# MultiWii_Board.net
KiCad netlist of a schematic drawn in EAGLE
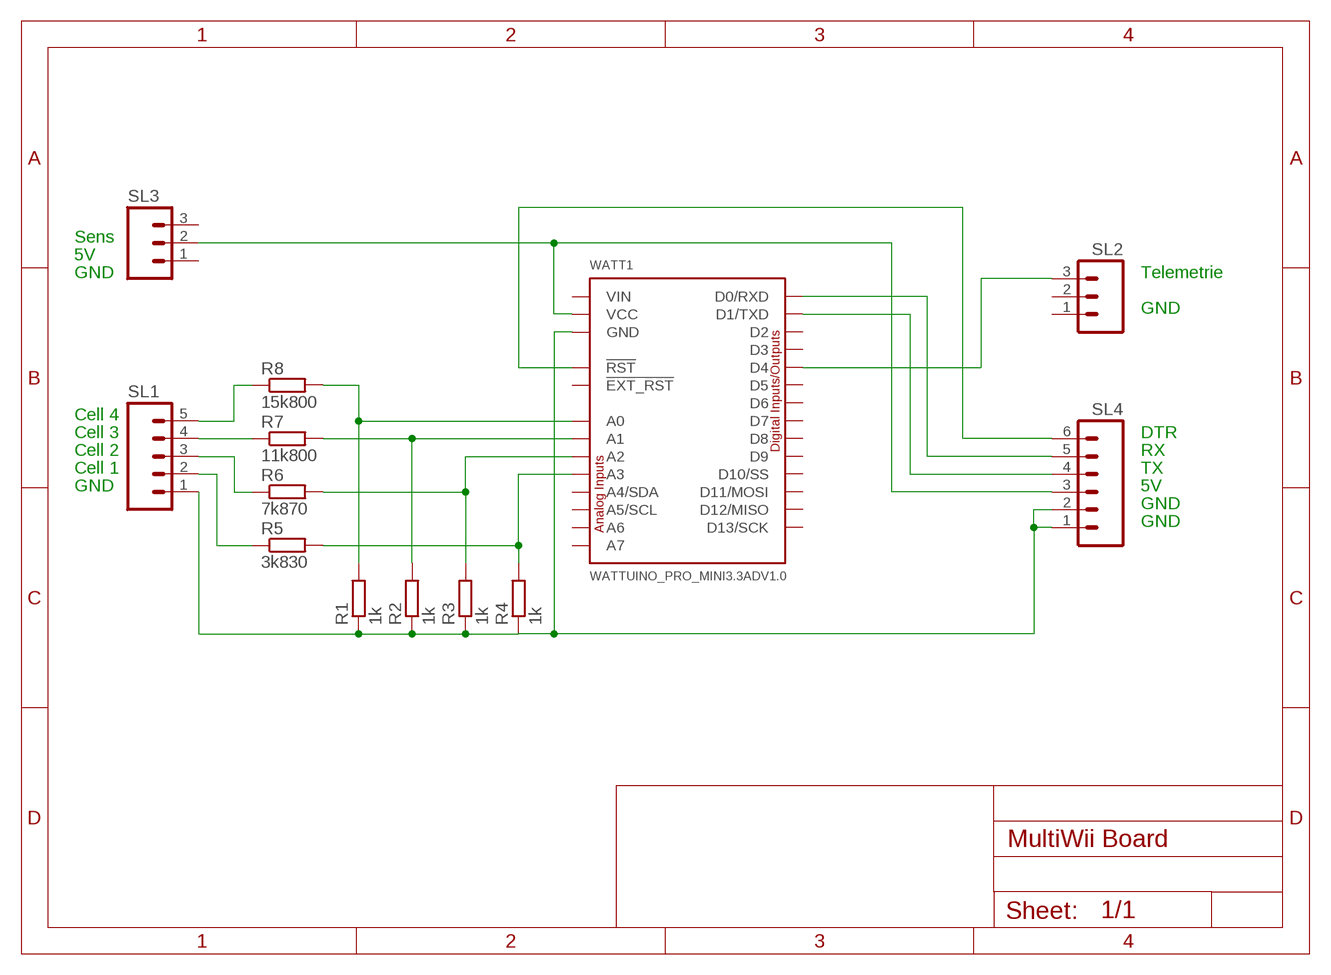
[diagram p0: schematic, sheet 1]

(export (version "E")
  (design (tool "Eeschema 10.0.6"))
  (components
    (comp (ref "R1")
      (value "1k")
      (footprint "eagle-import:0207_7")
      (libsource (lib "eagle-import") (part "R-EU_0207/7"))
    )
    (comp (ref "R2")
      (value "1k")
      (footprint "eagle-import:0207_7")
      (libsource (lib "eagle-import") (part "R-EU_0207/7"))
    )
    (comp (ref "R3")
      (value "1k")
      (footprint "eagle-import:0207_7")
      (libsource (lib "eagle-import") (part "R-EU_0207/7"))
    )
    (comp (ref "R4")
      (value "1k")
      (footprint "eagle-import:0207_7")
      (libsource (lib "eagle-import") (part "R-EU_0207/7"))
    )
    (comp (ref "R5")
      (value "3k830")
      (footprint "eagle-import:0207_7")
      (libsource (lib "eagle-import") (part "R-EU_0207/7"))
    )
    (comp (ref "R6")
      (value "7k870")
      (footprint "eagle-import:0207_7")
      (libsource (lib "eagle-import") (part "R-EU_0207/7"))
    )
    (comp (ref "R7")
      (value "11k800")
      (footprint "eagle-import:0207_7")
      (libsource (lib "eagle-import") (part "R-EU_0207/7"))
    )
    (comp (ref "R8")
      (value "15k800")
      (footprint "eagle-import:0207_7")
      (libsource (lib "eagle-import") (part "R-EU_0207/7"))
    )
    (comp (ref "SL1")
      (value "M05")
      (footprint "eagle-import:05P")
      (libsource (lib "eagle-import") (part "M05"))
    )
    (comp (ref "SL2")
      (value "M03")
      (footprint "eagle-import:03P")
      (libsource (lib "eagle-import") (part "M03"))
    )
    (comp (ref "SL3")
      (value "M03")
      (footprint "eagle-import:03P")
      (libsource (lib "eagle-import") (part "M03"))
    )
    (comp (ref "SL4")
      (value "M06")
      (footprint "eagle-import:06P")
      (libsource (lib "eagle-import") (part "M06"))
    )
    (comp (ref "WATT1")
      (value "WATTUINO_PRO_MINI3.3ADV1.0")
      (footprint "eagle-import:WATTUINO_PRO_MINI")
      (libsource (lib "eagle-import") (part "WATTUINO_PRO_MINIADV1.03.3"))
    )
  )
  (nets
    (net (code "1") (name "/VIN") (class "Default")
      (node (ref "WATT1") (pin "VIN") (pinfunction "VIN_VIN") (pintype "power_in"))
    )
    (net (code "2") (name "Net-(R1-Pad2)") (class "Default")
      (node (ref "R1") (pin "2") (pinfunction "2_2") (pintype "passive"))
      (node (ref "R8") (pin "2") (pinfunction "2_2") (pintype "passive"))
      (node (ref "WATT1") (pin "A0") (pinfunction "A0_A0") (pintype "input"))
    )
    (net (code "3") (name "Net-(R2-Pad2)") (class "Default")
      (node (ref "R2") (pin "2") (pinfunction "2_2") (pintype "passive"))
      (node (ref "R7") (pin "2") (pinfunction "2_2") (pintype "passive"))
      (node (ref "WATT1") (pin "A1") (pinfunction "A1_A1") (pintype "input"))
    )
    (net (code "4") (name "Net-(R3-Pad2)") (class "Default")
      (node (ref "R3") (pin "2") (pinfunction "2_2") (pintype "passive"))
      (node (ref "R6") (pin "2") (pinfunction "2_2") (pintype "passive"))
      (node (ref "WATT1") (pin "A2") (pinfunction "A2_A2") (pintype "input"))
    )
    (net (code "5") (name "Net-(R4-Pad2)") (class "Default")
      (node (ref "R4") (pin "2") (pinfunction "2_2") (pintype "passive"))
      (node (ref "R5") (pin "2") (pinfunction "2_2") (pintype "passive"))
      (node (ref "WATT1") (pin "A3") (pinfunction "A3_A3") (pintype "input"))
    )
    (net (code "6") (name "Net-(R5-Pad1)") (class "Default")
      (node (ref "R5") (pin "1") (pinfunction "1_1") (pintype "passive"))
      (node (ref "SL1") (pin "2") (pinfunction "2_2") (pintype "passive"))
    )
    (net (code "7") (name "Net-(R6-Pad1)") (class "Default")
      (node (ref "R6") (pin "1") (pinfunction "1_1") (pintype "passive"))
      (node (ref "SL1") (pin "3") (pinfunction "3_3") (pintype "passive"))
    )
    (net (code "8") (name "Net-(R7-Pad1)") (class "Default")
      (node (ref "R7") (pin "1") (pinfunction "1_1") (pintype "passive"))
      (node (ref "SL1") (pin "4") (pinfunction "4_4") (pintype "passive"))
    )
    (net (code "9") (name "Net-(R8-Pad1)") (class "Default")
      (node (ref "R8") (pin "1") (pinfunction "1_1") (pintype "passive"))
      (node (ref "SL1") (pin "5") (pinfunction "5_5") (pintype "passive"))
    )
    (net (code "10") (name "Net-(WATT1-D0{slash}RXD)") (class "Default")
      (node (ref "SL4") (pin "5") (pinfunction "5_5") (pintype "passive"))
      (node (ref "WATT1") (pin "RXD@1") (pinfunction "D0/RXD_RXD@1") (pintype "bidirectional"))
    )
    (net (code "11") (name "Net-(WATT1-D1{slash}TXD)") (class "Default")
      (node (ref "SL4") (pin "4") (pinfunction "4_4") (pintype "passive"))
      (node (ref "WATT1") (pin "TXD@1") (pinfunction "D1/TXD_TXD@1") (pintype "bidirectional"))
    )
    (net (code "12") (name "Net-(WATT1-D4)") (class "Default")
      (node (ref "SL2") (pin "3") (pinfunction "3_3") (pintype "passive"))
      (node (ref "WATT1") (pin "4") (pinfunction "D4_4") (pintype "bidirectional"))
    )
    (net (code "13") (name "Net-(WATT1-GND)") (class "Default")
      (node (ref "R1") (pin "1") (pinfunction "1_1") (pintype "passive"))
      (node (ref "R2") (pin "1") (pinfunction "1_1") (pintype "passive"))
      (node (ref "R3") (pin "1") (pinfunction "1_1") (pintype "passive"))
      (node (ref "R4") (pin "1") (pinfunction "1_1") (pintype "passive"))
      (node (ref "SL1") (pin "1") (pinfunction "1_1") (pintype "passive"))
      (node (ref "SL4") (pin "1") (pinfunction "1_1") (pintype "passive"))
      (node (ref "SL4") (pin "2") (pinfunction "2_2") (pintype "passive"))
      (node (ref "WATT1") (pin "GND@1") (pinfunction "GND_GND@1") (pintype "power_in"))
    )
    (net (code "14") (name "Net-(WATT1-VCC)") (class "Default")
      (node (ref "SL3") (pin "2") (pinfunction "2_2") (pintype "passive"))
      (node (ref "SL4") (pin "3") (pinfunction "3_3") (pintype "passive"))
      (node (ref "WATT1") (pin "VCC@1") (pinfunction "VCC_VCC@1") (pintype "power_in"))
    )
    (net (code "15") (name "Net-(WATT1-~{RST})") (class "Default")
      (node (ref "SL4") (pin "6") (pinfunction "6_6") (pintype "passive"))
      (node (ref "WATT1") (pin "RST@1") (pinfunction "~{RST}_RST@1") (pintype "input"))
    )
    (net (code "16") (name "unconnected-(SL2-Pad1)") (class "Default")
      (node (ref "SL2") (pin "1") (pinfunction "1_1") (pintype "passive"))
    )
    (net (code "17") (name "unconnected-(SL2-Pad2)") (class "Default")
      (node (ref "SL2") (pin "2") (pinfunction "2_2") (pintype "passive"))
    )
    (net (code "18") (name "unconnected-(SL3-Pad1)") (class "Default")
      (node (ref "SL3") (pin "1") (pinfunction "1_1") (pintype "passive"))
    )
    (net (code "19") (name "unconnected-(SL3-Pad3)") (class "Default")
      (node (ref "SL3") (pin "3") (pinfunction "3_3") (pintype "passive"))
    )
    (net (code "20") (name "unconnected-(WATT1-A4{slash}SDA-PadA4)") (class "Default")
      (node (ref "WATT1") (pin "A4") (pinfunction "A4/SDA_A4") (pintype "input"))
    )
    (net (code "21") (name "unconnected-(WATT1-A5{slash}SCL-PadA5)") (class "Default")
      (node (ref "WATT1") (pin "A5") (pinfunction "A5/SCL_A5") (pintype "input"))
    )
    (net (code "22") (name "unconnected-(WATT1-D2-Pad2)") (class "Default")
      (node (ref "WATT1") (pin "2") (pinfunction "D2_2") (pintype "bidirectional"))
    )
    (net (code "23") (name "unconnected-(WATT1-D3-Pad3)") (class "Default")
      (node (ref "WATT1") (pin "3") (pinfunction "D3_3") (pintype "bidirectional"))
    )
    (net (code "24") (name "unconnected-(WATT1-D5-Pad5)") (class "Default")
      (node (ref "WATT1") (pin "5") (pinfunction "D5_5") (pintype "bidirectional"))
    )
    (net (code "25") (name "unconnected-(WATT1-D6-Pad6)") (class "Default")
      (node (ref "WATT1") (pin "6") (pinfunction "D6_6") (pintype "bidirectional"))
    )
    (net (code "26") (name "unconnected-(WATT1-D7-Pad7)") (class "Default")
      (node (ref "WATT1") (pin "7") (pinfunction "D7_7") (pintype "bidirectional"))
    )
    (net (code "27") (name "unconnected-(WATT1-D8-Pad8)") (class "Default")
      (node (ref "WATT1") (pin "8") (pinfunction "D8_8") (pintype "bidirectional"))
    )
    (net (code "28") (name "unconnected-(WATT1-D9-Pad9)") (class "Default")
      (node (ref "WATT1") (pin "9") (pinfunction "D9_9") (pintype "bidirectional"))
    )
    (net (code "29") (name "unconnected-(WATT1-D10{slash}SS-Pad10)") (class "Default")
      (node (ref "WATT1") (pin "10") (pinfunction "D10/SS_10") (pintype "bidirectional"))
    )
    (net (code "30") (name "unconnected-(WATT1-D11{slash}MOSI-Pad11)") (class "Default")
      (node (ref "WATT1") (pin "11") (pinfunction "D11/MOSI_11") (pintype "bidirectional"))
    )
    (net (code "31") (name "unconnected-(WATT1-D12{slash}MISO-Pad12)") (class "Default")
      (node (ref "WATT1") (pin "12") (pinfunction "D12/MISO_12") (pintype "bidirectional"))
    )
    (net (code "32") (name "unconnected-(WATT1-D13{slash}SCK-Pad13)") (class "Default")
      (node (ref "WATT1") (pin "13") (pinfunction "D13/SCK_13") (pintype "bidirectional"))
    )
    (net (code "33") (name "unconnected-(WATT1-PadA6)") (class "Default")
      (node (ref "WATT1") (pin "A6") (pinfunction "A6_A6") (pintype "input"))
    )
    (net (code "34") (name "unconnected-(WATT1-PadA7)") (class "Default")
      (node (ref "WATT1") (pin "A7") (pinfunction "A7_A7") (pintype "input"))
    )
    (net (code "35") (name "unconnected-(WATT1-~{EXT_RST}-PadEXT_RST)") (class "Default")
      (node (ref "WATT1") (pin "EXT_RST") (pinfunction "~{EXT_RST}_EXT_RST") (pintype "bidirectional"))
    )
  )
)
